# RELAY.net
KiCad netlist of a schematic drawn in Altium Designer
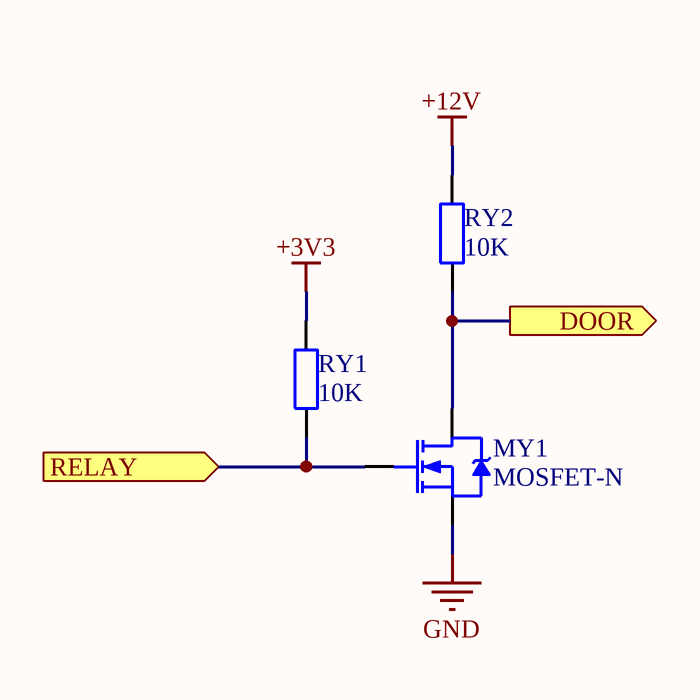
[diagram p0: RELAY.SchDoc]

(export (version "E")
  (design (tool "Eeschema 10.0.6"))
  (components
    (comp (ref "MY1") (value "MOSFET-N") (footprint "SOT23_N") (libsource (lib "Peace的集成库") (part "SI2300")))
    (comp (ref "RY1")
      (value "10K")
      (footprint "RESC1608N")
      (description "Resistor")
      (fields (field (name "Comment") "Res1") (field (name "PUBLISHER") "Altium Limited"))
      (libsource (lib "Peace的集成库") (part "Res1"))
    )
    (comp (ref "RY2")
      (value "10K")
      (footprint "RESC1608N")
      (description "Resistor")
      (fields (field (name "Comment") "Res1") (field (name "PUBLISHER") "Altium Limited"))
      (libsource (lib "Peace的集成库") (part "Res1"))
    )
  )
  (nets
    (net (code "1") (name "+3V3") (class "Default")
      (node (ref "RY1") (pin "2") (pinfunction "2_2") (pintype "passive"))
    )
    (net (code "2") (name "+12V") (class "Default")
      (node (ref "RY2") (pin "2") (pinfunction "2_2") (pintype "passive"))
    )
    (net (code "3") (name "/DOOR") (class "Default")
      (node (ref "MY1") (pin "1") (pinfunction "D_1") (pintype "passive"))
      (node (ref "RY2") (pin "1") (pinfunction "1_1") (pintype "passive"))
    )
    (net (code "4") (name "/RELAY") (class "Default")
      (node (ref "MY1") (pin "3") (pinfunction "G_3") (pintype "passive"))
      (node (ref "RY1") (pin "1") (pinfunction "1_1") (pintype "passive"))
    )
    (net (code "5") (name "GND") (class "Default")
      (node (ref "MY1") (pin "2") (pinfunction "S_2") (pintype "passive"))
    )
  )
)
